# Top.net
KiCad netlist of a schematic drawn in Altium Designer
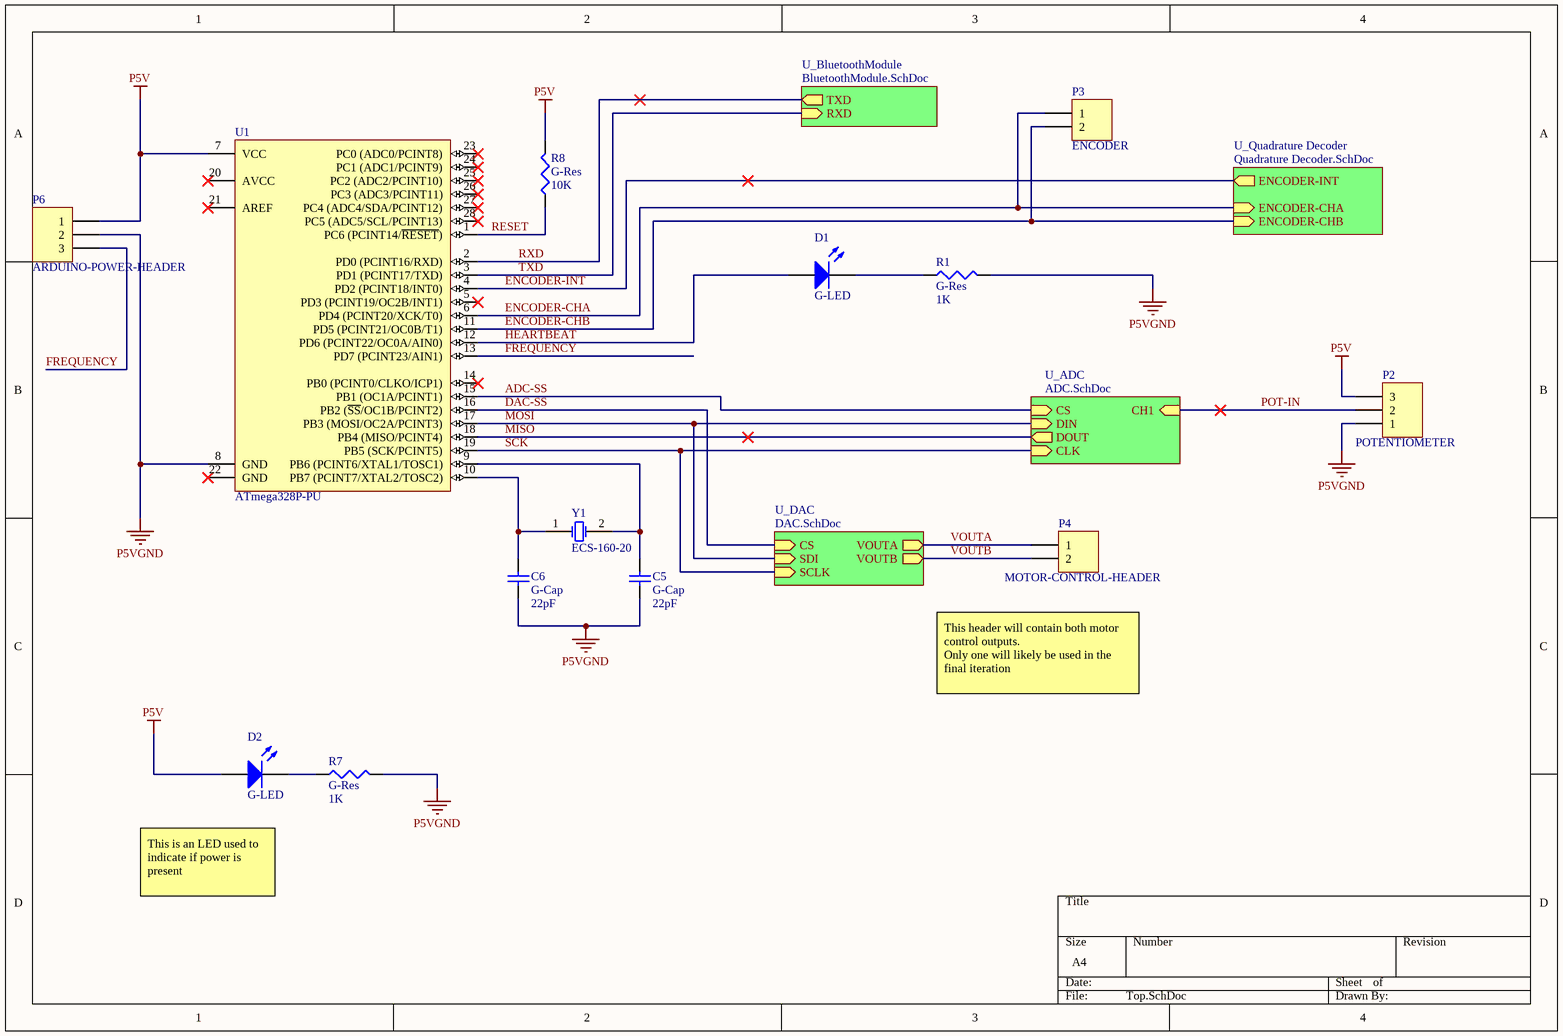
[diagram p0: Top.SchDoc]

(export (version "E")
  (design (tool "Eeschema 10.0.6"))
  (components
    (comp (ref "C5")
      (value "G-Cap")
      (footprint "Cap2.54mm_LGE1.0")
      (description "capacitor (specify value)")
      (fields (field (name "ALTIUM_VALUE") "22pF") (field (name "PUBLISHER") "Altium Limited"))
      (libsource (lib "PartsDatabaseV13p4") (part "G-Cap"))
    )
    (comp (ref "C6")
      (value "G-Cap")
      (footprint "Cap2.54mm_LGE1.0")
      (description "capacitor (specify value)")
      (fields (field (name "ALTIUM_VALUE") "22pF") (field (name "PUBLISHER") "Altium Limited"))
      (libsource (lib "PartsDatabaseV13p4") (part "G-Cap"))
    )
    (comp (ref "D1")
      (value "G-LED")
      (footprint "LED_LGE1.0")
      (description "Typical RED, GREEN, YELLOW, AMBER GaAs LED")
      (fields (field (name "PUBLISHER") "Altium Limited"))
      (libsource (lib "PartsDatabaseV13p4") (part "G-LED"))
    )
    (comp (ref "D2")
      (value "G-LED")
      (footprint "LED_LGE1.0")
      (description "Typical RED, GREEN, YELLOW, AMBER GaAs LED")
      (fields (field (name "PUBLISHER") "Altium Limited"))
      (libsource (lib "PartsDatabaseV13p4") (part "G-LED"))
    )
    (comp (ref "P2")
      (value "POTENTIOMETER")
      (footprint "HDR1X3_LGE1.0")
      (description "Header, 4-Pin")
      (fields (field (name "PUBLISHER") "Altium Limited"))
      (libsource (lib "") (part "C-Hdr1x3_1"))
    )
    (comp (ref "P3")
      (value "ENCODER")
      (footprint "HDR1X2_LGE1.0")
      (description "Header, 2-Pin")
      (fields (field (name "PUBLISHER") "Altium Limited"))
      (libsource (lib "PartsDatabaseV13p4") (part "C-Hdr1x2"))
    )
    (comp (ref "P4")
      (value "MOTOR-CONTROL-HEADER")
      (footprint "HDR1X2_LGE1.0")
      (description "Header, 2-Pin")
      (fields (field (name "PUBLISHER") "Altium Limited"))
      (libsource (lib "PartsDatabaseV13p4") (part "C-Hdr1x2"))
    )
    (comp (ref "P6")
      (value "ARDUINO-POWER-HEADER")
      (footprint "HDR1X3_LGE1.0")
      (description "Header, 4-Pin")
      (fields (field (name "PUBLISHER") "Altium Limited"))
      (libsource (lib "PartsDatabaseV13p4") (part "C-Hdr1x3"))
    )
    (comp (ref "R1")
      (value "G-Res")
      (footprint "Res2.54mm_LGE1.0")
      (description "resistor (specify value)")
      (fields (field (name "ALTIUM_VALUE") "1K") (field (name "PUBLISHER") "Altium Limited"))
      (libsource (lib "PartsDatabaseV13p4") (part "G-Res"))
    )
    (comp (ref "R7")
      (value "G-Res")
      (footprint "Res2.54mm_LGE1.0")
      (description "resistor (specify value)")
      (fields (field (name "ALTIUM_VALUE") "1K") (field (name "PUBLISHER") "Altium Limited"))
      (libsource (lib "PartsDatabaseV13p4") (part "G-Res"))
    )
    (comp (ref "R8")
      (value "G-Res")
      (footprint "Res2.54mm_LGE1.0")
      (description "resistor (specify value)")
      (fields (field (name "ALTIUM_VALUE") "10K") (field (name "PUBLISHER") "Altium Limited"))
      (libsource (lib "PartsDatabaseV13p4") (part "G-Res"))
    )
    (comp (ref "U1")
      (value "ATmega328P-PU")
      (footprint "ISDIP16_LGE1.0")
      (fields (field (name "PUBLISHER") "Altium Limited"))
      (libsource (lib "Atmel Microcontroller 8-Bit megaAVR") (part "ATmega328P-PU"))
    )
    (comp (ref "Y1")
      (value "ECS-160-20")
      (footprint "HC-49U")
      (description "Crystal Oscillator")
      (fields (field (name "PUBLISHER") "Altium Limited"))
      (libsource (lib "ECS Crystal Oscillator") (part "ECS-200-20-1"))
    )
  )
  (nets
    (net (code "1") (name "/ADC-SS") (class "Default")
      (node (ref "U1") (pin "15") (pinfunction "PB1_(OC1A/PCINT1)_15") (pintype "bidirectional"))
    )
    (net (code "2") (name "/DAC-SS") (class "Default")
      (node (ref "U1") (pin "16") (pinfunction "PB2_(~{SS}/OC1B/PCINT2)_16") (pintype "bidirectional"))
    )
    (net (code "3") (name "/ENCODER-CHA") (class "Default")
      (node (ref "P3") (pin "1") (pinfunction "1_1") (pintype "passive"))
      (node (ref "U1") (pin "6") (pinfunction "PD4_(PCINT20/XCK/T0)_6") (pintype "bidirectional"))
    )
    (net (code "4") (name "/ENCODER-CHB") (class "Default")
      (node (ref "P3") (pin "2") (pinfunction "2_2") (pintype "passive"))
      (node (ref "U1") (pin "11") (pinfunction "PD5_(PCINT21/OC0B/T1)_11") (pintype "bidirectional"))
    )
    (net (code "5") (name "/ENCODER-INT") (class "Default")
      (node (ref "U1") (pin "4") (pinfunction "PD2_(PCINT18/INT0)_4") (pintype "bidirectional+no_connect"))
    )
    (net (code "6") (name "/FREQUENCY") (class "Default")
      (node (ref "P6") (pin "3") (pinfunction "3_3") (pintype "passive"))
      (node (ref "U1") (pin "13") (pinfunction "PD7_(PCINT23/AIN1)_13") (pintype "bidirectional"))
    )
    (net (code "7") (name "/HEARTBEAT") (class "Default")
      (node (ref "D1") (pin "1") (pinfunction "A_1") (pintype "passive"))
      (node (ref "U1") (pin "12") (pinfunction "PD6_(PCINT22/OC0A/AIN0)_12") (pintype "bidirectional"))
    )
    (net (code "8") (name "/MISO") (class "Default")
      (node (ref "U1") (pin "18") (pinfunction "PB4_(MISO/PCINT4)_18") (pintype "bidirectional+no_connect"))
    )
    (net (code "9") (name "/MOSI") (class "Default")
      (node (ref "U1") (pin "17") (pinfunction "PB3_(MOSI/OC2A/PCINT3)_17") (pintype "bidirectional"))
    )
    (net (code "10") (name "/POT-IN") (class "Default")
      (node (ref "P2") (pin "2") (pinfunction "2_2") (pintype "passive+no_connect"))
    )
    (net (code "11") (name "/RESET") (class "Default")
      (node (ref "R8") (pin "1") (pinfunction "1_1") (pintype "passive"))
      (node (ref "U1") (pin "1") (pinfunction "PC6_(PCINT14/~{RESET})_1") (pintype "bidirectional"))
    )
    (net (code "12") (name "/RXD") (class "Default")
      (node (ref "U1") (pin "2") (pinfunction "PD0_(PCINT16/RXD)_2") (pintype "bidirectional"))
    )
    (net (code "13") (name "/SCK") (class "Default")
      (node (ref "U1") (pin "19") (pinfunction "PB5_(SCK/PCINT5)_19") (pintype "bidirectional"))
    )
    (net (code "14") (name "/TXD") (class "Default")
      (node (ref "U1") (pin "3") (pinfunction "PD1_(PCINT17/TXD)_3") (pintype "bidirectional"))
    )
    (net (code "15") (name "/VOUTA") (class "Default")
      (node (ref "P4") (pin "1") (pinfunction "1_1") (pintype "passive"))
    )
    (net (code "16") (name "/VOUTB") (class "Default")
      (node (ref "P4") (pin "2") (pinfunction "2_2") (pintype "passive"))
    )
    (net (code "17") (name "Net-(D1-K)") (class "Default")
      (node (ref "D1") (pin "2") (pinfunction "K_2") (pintype "passive"))
      (node (ref "R1") (pin "1") (pinfunction "1_1") (pintype "passive"))
    )
    (net (code "18") (name "Net-(D2-K)") (class "Default")
      (node (ref "D2") (pin "2") (pinfunction "K_2") (pintype "passive"))
      (node (ref "R7") (pin "1") (pinfunction "1_1") (pintype "passive"))
    )
    (net (code "19") (name "Net-(U1-PB6_(PCINT6{slash}XTAL1{slash}TOSC1))") (class "Default")
      (node (ref "C5") (pin "2") (pinfunction "2_2") (pintype "passive"))
      (node (ref "U1") (pin "9") (pinfunction "PB6_(PCINT6/XTAL1/TOSC1)_9") (pintype "bidirectional"))
      (node (ref "Y1") (pin "2") (pinfunction "OSC2_2") (pintype "passive"))
    )
    (net (code "20") (name "Net-(U1-PB7_(PCINT7{slash}XTAL2{slash}TOSC2))") (class "Default")
      (node (ref "C6") (pin "2") (pinfunction "2_2") (pintype "passive"))
      (node (ref "U1") (pin "10") (pinfunction "PB7_(PCINT7/XTAL2/TOSC2)_10") (pintype "bidirectional"))
      (node (ref "Y1") (pin "1") (pinfunction "OSC1_1") (pintype "passive"))
    )
    (net (code "21") (name "P5V") (class "Default")
      (node (ref "D2") (pin "1") (pinfunction "A_1") (pintype "passive"))
      (node (ref "P2") (pin "3") (pinfunction "3_3") (pintype "passive"))
      (node (ref "P6") (pin "1") (pinfunction "1_1") (pintype "passive"))
      (node (ref "R8") (pin "2") (pinfunction "2_2") (pintype "passive"))
      (node (ref "U1") (pin "7") (pinfunction "VCC_7") (pintype "power_in"))
    )
    (net (code "22") (name "P5VGND") (class "Default")
      (node (ref "C5") (pin "1") (pinfunction "1_1") (pintype "passive"))
      (node (ref "C6") (pin "1") (pinfunction "1_1") (pintype "passive"))
      (node (ref "P2") (pin "1") (pinfunction "1_1") (pintype "passive"))
      (node (ref "P6") (pin "2") (pinfunction "2_2") (pintype "passive"))
      (node (ref "R1") (pin "2") (pinfunction "2_2") (pintype "passive"))
      (node (ref "R7") (pin "2") (pinfunction "2_2") (pintype "passive"))
      (node (ref "U1") (pin "8") (pinfunction "GND_8") (pintype "power_in"))
    )
    (net (code "23") (name "unconnected-(U1-AREF-Pad21)") (class "Default")
      (node (ref "U1") (pin "21") (pinfunction "AREF_21") (pintype "power_in+no_connect"))
    )
    (net (code "24") (name "unconnected-(U1-AVCC-Pad20)") (class "Default")
      (node (ref "U1") (pin "20") (pinfunction "AVCC_20") (pintype "power_in+no_connect"))
    )
    (net (code "25") (name "unconnected-(U1-GND-Pad22)") (class "Default")
      (node (ref "U1") (pin "22") (pinfunction "GND_22") (pintype "power_in+no_connect"))
    )
    (net (code "26") (name "unconnected-(U1-PB0_(PCINT0{slash}CLKO{slash}ICP1)-Pad14)") (class "Default")
      (node (ref "U1") (pin "14") (pinfunction "PB0_(PCINT0/CLKO/ICP1)_14") (pintype "bidirectional+no_connect"))
    )
    (net (code "27") (name "unconnected-(U1-PC0_(ADC0{slash}PCINT8)-Pad23)") (class "Default")
      (node (ref "U1") (pin "23") (pinfunction "PC0_(ADC0/PCINT8)_23") (pintype "bidirectional+no_connect"))
    )
    (net (code "28") (name "unconnected-(U1-PC1_(ADC1{slash}PCINT9)-Pad24)") (class "Default")
      (node (ref "U1") (pin "24") (pinfunction "PC1_(ADC1/PCINT9)_24") (pintype "bidirectional+no_connect"))
    )
    (net (code "29") (name "unconnected-(U1-PC2_(ADC2{slash}PCINT10)-Pad25)") (class "Default")
      (node (ref "U1") (pin "25") (pinfunction "PC2_(ADC2/PCINT10)_25") (pintype "bidirectional+no_connect"))
    )
    (net (code "30") (name "unconnected-(U1-PC3_(ADC3{slash}PCINT11)-Pad26)") (class "Default")
      (node (ref "U1") (pin "26") (pinfunction "PC3_(ADC3/PCINT11)_26") (pintype "bidirectional+no_connect"))
    )
    (net (code "31") (name "unconnected-(U1-PC4_(ADC4{slash}SDA{slash}PCINT12)-Pad27)") (class "Default")
      (node (ref "U1") (pin "27") (pinfunction "PC4_(ADC4/SDA/PCINT12)_27") (pintype "bidirectional+no_connect"))
    )
    (net (code "32") (name "unconnected-(U1-PC5_(ADC5{slash}SCL{slash}PCINT13)-Pad28)") (class "Default")
      (node (ref "U1") (pin "28") (pinfunction "PC5_(ADC5/SCL/PCINT13)_28") (pintype "bidirectional+no_connect"))
    )
    (net (code "33") (name "unconnected-(U1-PD3_(PCINT19{slash}OC2B{slash}INT1)-Pad5)") (class "Default")
      (node (ref "U1") (pin "5") (pinfunction "PD3_(PCINT19/OC2B/INT1)_5") (pintype "bidirectional+no_connect"))
    )
  )
)
